# SCH_WifiNode.net
KiCad netlist of a schematic drawn in Altium Designer
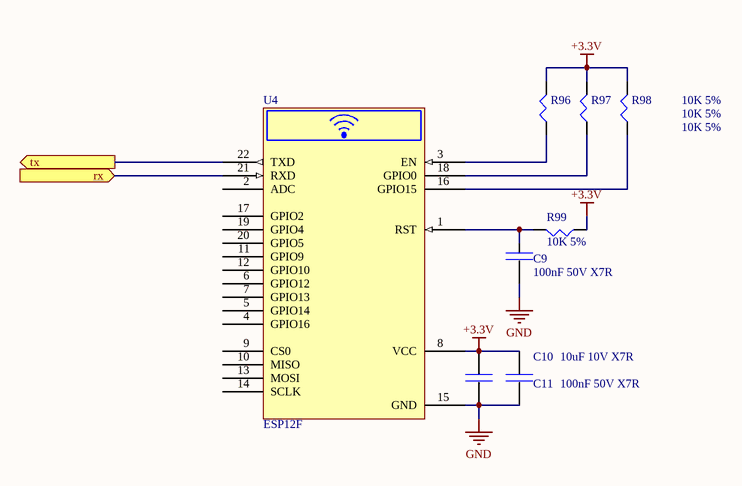
[diagram p0: SCH_WifiNode.SchDoc]

(export (version "E")
  (design (tool "Eeschema 10.0.6"))
  (components
    (comp (ref "C9")
      (value "100nF 50V X7R")
      (footprint "C_0805")
      (description "100nF x 50v")
      (libsource (lib "IDCI_WifiNode_2_R00") (part "Capacitor"))
    )
    (comp (ref "C10")
      (value "10uF 10V X7R")
      (footprint "C_0805")
      (description "100nF x 50v")
      (libsource (lib "IDCI_WifiNode_2_R00") (part "Capacitor"))
    )
    (comp (ref "C11")
      (value "100nF 50V X7R")
      (footprint "C_0805")
      (description "100nF x 50v")
      (libsource (lib "IDCI_WifiNode_2_R00") (part "Capacitor"))
    )
    (comp (ref "R96")
      (value "10K 5%")
      (footprint "R_0805")
      (libsource (lib "IDCI_WifiNode_2_R00") (part "Resistor"))
    )
    (comp (ref "R97")
      (value "10K 5%")
      (footprint "R_0805")
      (libsource (lib "IDCI_WifiNode_2_R00") (part "Resistor"))
    )
    (comp (ref "R98")
      (value "10K 5%")
      (footprint "R_0805")
      (libsource (lib "IDCI_WifiNode_2_R00") (part "Resistor"))
    )
    (comp (ref "R99")
      (value "10K 5%")
      (footprint "R_0805")
      (libsource (lib "IDCI_WifiNode_2_R00") (part "Resistor"))
    )
    (comp (ref "U4")
      (value "ESP12F")
      (footprint "ESP12F")
      (description "Wifi Module")
      (libsource (lib "IDCI_WifiNode_2_R00") (part "ESP12F Wifi Module"))
    )
  )
  (nets
    (net (code "1") (name "+3.3V") (class "Default")
      (node (ref "C10") (pin "2") (pinfunction "2_2") (pintype "passive"))
      (node (ref "C11") (pin "2") (pinfunction "2_2") (pintype "passive"))
      (node (ref "R96") (pin "2") (pinfunction "2_2") (pintype "passive"))
      (node (ref "R97") (pin "2") (pinfunction "2_2") (pintype "passive"))
      (node (ref "R98") (pin "2") (pinfunction "2_2") (pintype "passive"))
      (node (ref "R99") (pin "1") (pinfunction "1_1") (pintype "passive"))
      (node (ref "U4") (pin "8") (pinfunction "VCC_8") (pintype "power_in"))
    )
    (net (code "2") (name "/rx") (class "Default")
      (node (ref "U4") (pin "21") (pinfunction "RXD_21") (pintype "input"))
    )
    (net (code "3") (name "/tx") (class "Default")
      (node (ref "U4") (pin "22") (pinfunction "TXD_22") (pintype "output"))
    )
    (net (code "4") (name "GND") (class "Default")
      (node (ref "C10") (pin "1") (pinfunction "1_1") (pintype "passive"))
      (node (ref "C11") (pin "1") (pinfunction "1_1") (pintype "passive"))
      (node (ref "C9") (pin "1") (pinfunction "1_1") (pintype "passive"))
      (node (ref "U4") (pin "15") (pinfunction "GND_15") (pintype "power_in"))
    )
    (net (code "5") (name "Net-(U4-EN)") (class "Default")
      (node (ref "R96") (pin "1") (pinfunction "1_1") (pintype "passive"))
      (node (ref "U4") (pin "3") (pinfunction "EN_3") (pintype "input"))
    )
    (net (code "6") (name "Net-(U4-GPIO0)") (class "Default")
      (node (ref "R97") (pin "1") (pinfunction "1_1") (pintype "passive"))
      (node (ref "U4") (pin "18") (pinfunction "GPIO0_18") (pintype "passive"))
    )
    (net (code "7") (name "Net-(U4-GPIO15)") (class "Default")
      (node (ref "R98") (pin "1") (pinfunction "1_1") (pintype "passive"))
      (node (ref "U4") (pin "16") (pinfunction "GPIO15_16") (pintype "passive"))
    )
    (net (code "8") (name "Net-(U4-RST)") (class "Default")
      (node (ref "C9") (pin "2") (pinfunction "2_2") (pintype "passive"))
      (node (ref "R99") (pin "2") (pinfunction "2_2") (pintype "passive"))
      (node (ref "U4") (pin "1") (pinfunction "RST_1") (pintype "input"))
    )
    (net (code "9") (name "unconnected-(U4-ADC-Pad2)") (class "Default")
      (node (ref "U4") (pin "2") (pinfunction "ADC_2") (pintype "passive"))
    )
    (net (code "10") (name "unconnected-(U4-CS0-Pad9)") (class "Default")
      (node (ref "U4") (pin "9") (pinfunction "CS0_9") (pintype "passive"))
    )
    (net (code "11") (name "unconnected-(U4-GPIO2-Pad17)") (class "Default")
      (node (ref "U4") (pin "17") (pinfunction "GPIO2_17") (pintype "passive"))
    )
    (net (code "12") (name "unconnected-(U4-GPIO4-Pad19)") (class "Default")
      (node (ref "U4") (pin "19") (pinfunction "GPIO4_19") (pintype "passive"))
    )
    (net (code "13") (name "unconnected-(U4-GPIO5-Pad20)") (class "Default")
      (node (ref "U4") (pin "20") (pinfunction "GPIO5_20") (pintype "passive"))
    )
    (net (code "14") (name "unconnected-(U4-GPIO9-Pad11)") (class "Default")
      (node (ref "U4") (pin "11") (pinfunction "GPIO9_11") (pintype "passive"))
    )
    (net (code "15") (name "unconnected-(U4-GPIO10-Pad12)") (class "Default")
      (node (ref "U4") (pin "12") (pinfunction "GPIO10_12") (pintype "passive"))
    )
    (net (code "16") (name "unconnected-(U4-GPIO12-Pad6)") (class "Default")
      (node (ref "U4") (pin "6") (pinfunction "GPIO12_6") (pintype "passive"))
    )
    (net (code "17") (name "unconnected-(U4-GPIO13-Pad7)") (class "Default")
      (node (ref "U4") (pin "7") (pinfunction "GPIO13_7") (pintype "passive"))
    )
    (net (code "18") (name "unconnected-(U4-GPIO14-Pad5)") (class "Default")
      (node (ref "U4") (pin "5") (pinfunction "GPIO14_5") (pintype "passive"))
    )
    (net (code "19") (name "unconnected-(U4-GPIO16-Pad4)") (class "Default")
      (node (ref "U4") (pin "4") (pinfunction "GPIO16_4") (pintype "passive"))
    )
    (net (code "20") (name "unconnected-(U4-MISO-Pad10)") (class "Default")
      (node (ref "U4") (pin "10") (pinfunction "MISO_10") (pintype "passive"))
    )
    (net (code "21") (name "unconnected-(U4-MOSI-Pad13)") (class "Default")
      (node (ref "U4") (pin "13") (pinfunction "MOSI_13") (pintype "passive"))
    )
    (net (code "22") (name "unconnected-(U4-SCLK-Pad14)") (class "Default")
      (node (ref "U4") (pin "14") (pinfunction "SCLK_14") (pintype "passive"))
    )
  )
)
